# keypad_encoder.net
KiCad netlist of a schematic drawn in EAGLE
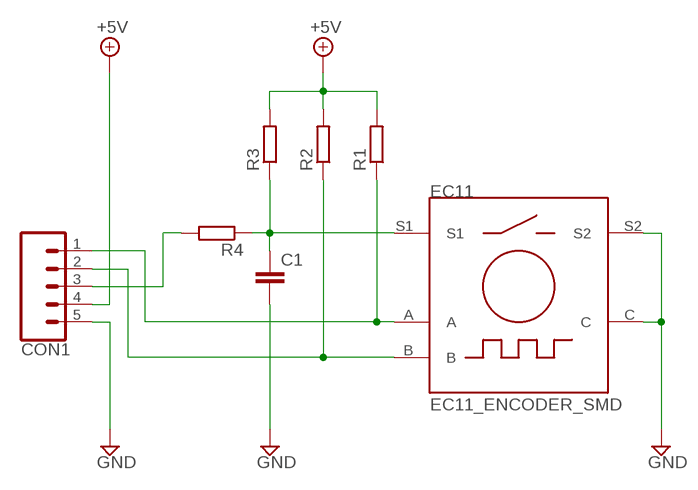
[diagram p0: schematic, sheet 1]

(export (version "E")
  (design (tool "Eeschema 10.0.6"))
  (components
    (comp (ref "C1")
      (value "C-EUC0603")
      (footprint "eagle-import:C0603")
      (libsource (lib "eagle-import") (part "C-EUC0603"))
    )
    (comp (ref "CON1")
      (value "CONN_05")
      (footprint "eagle-import:1X05")
      (libsource (lib "eagle-import") (part "CONN_05"))
    )
    (comp (ref "EC11")
      (value "EC11_ENCODER_SMD")
      (footprint "eagle-import:EC11_SMD")
      (libsource (lib "eagle-import") (part "EC11_ENCODER_SMD"))
    )
    (comp (ref "R1")
      (value "R-EU_R0603")
      (footprint "eagle-import:R0603")
      (libsource (lib "eagle-import") (part "R-EU_R0603"))
    )
    (comp (ref "R2")
      (value "R-EU_R0603")
      (footprint "eagle-import:R0603")
      (libsource (lib "eagle-import") (part "R-EU_R0603"))
    )
    (comp (ref "R3")
      (value "R-EU_R0603")
      (footprint "eagle-import:R0603")
      (libsource (lib "eagle-import") (part "R-EU_R0603"))
    )
    (comp (ref "R4")
      (value "R-EU_R0603")
      (footprint "eagle-import:R0603")
      (libsource (lib "eagle-import") (part "R-EU_R0603"))
    )
  )
  (nets
    (net (code "1") (name "+5V") (class "Default")
      (node (ref "CON1") (pin "4") (pinfunction "4_4") (pintype "passive"))
      (node (ref "R1") (pin "2") (pinfunction "2_2") (pintype "passive"))
      (node (ref "R2") (pin "2") (pinfunction "2_2") (pintype "passive"))
      (node (ref "R3") (pin "2") (pinfunction "2_2") (pintype "passive"))
    )
    (net (code "2") (name "GND") (class "Default")
      (node (ref "C1") (pin "2") (pinfunction "2_2") (pintype "passive"))
      (node (ref "CON1") (pin "5") (pinfunction "5_5") (pintype "passive"))
      (node (ref "EC11") (pin "C") (pinfunction "C_C") (pintype "bidirectional"))
      (node (ref "EC11") (pin "S2") (pinfunction "S2_S2") (pintype "bidirectional"))
    )
    (net (code "3") (name "Net-(C1-Pad1)") (class "Default")
      (node (ref "C1") (pin "1") (pinfunction "1_1") (pintype "passive"))
      (node (ref "EC11") (pin "S1") (pinfunction "S1_S1") (pintype "bidirectional"))
      (node (ref "R3") (pin "1") (pinfunction "1_1") (pintype "passive"))
      (node (ref "R4") (pin "1") (pinfunction "1_1") (pintype "passive"))
    )
    (net (code "4") (name "Net-(CON1-Pad1)") (class "Default")
      (node (ref "CON1") (pin "1") (pinfunction "1_1") (pintype "passive"))
      (node (ref "EC11") (pin "A") (pinfunction "A_A") (pintype "bidirectional"))
      (node (ref "R1") (pin "1") (pinfunction "1_1") (pintype "passive"))
    )
    (net (code "5") (name "Net-(CON1-Pad2)") (class "Default")
      (node (ref "CON1") (pin "2") (pinfunction "2_2") (pintype "passive"))
      (node (ref "EC11") (pin "B") (pinfunction "B_B") (pintype "bidirectional"))
      (node (ref "R2") (pin "1") (pinfunction "1_1") (pintype "passive"))
    )
    (net (code "6") (name "Net-(CON1-Pad3)") (class "Default")
      (node (ref "CON1") (pin "3") (pinfunction "3_3") (pintype "passive"))
      (node (ref "R4") (pin "2") (pinfunction "2_2") (pintype "passive"))
    )
  )
)
